# RFID_DC_Motor_Stm32.net
KiCad netlist of a schematic drawn in Altium Designer
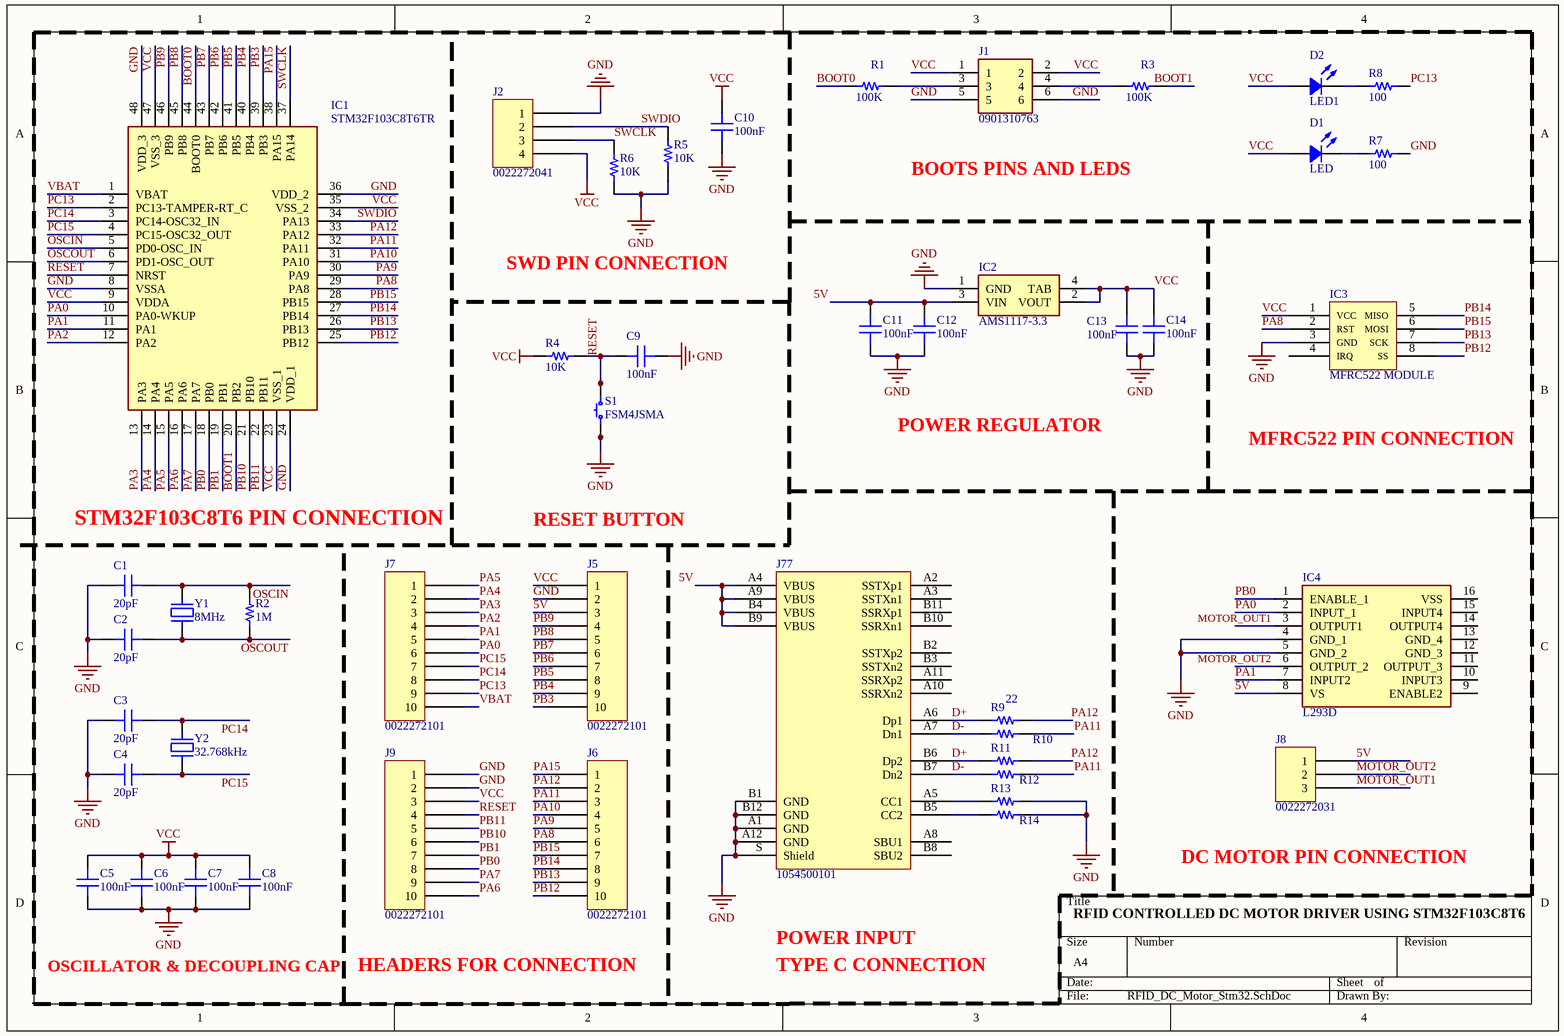
[diagram p0: RFID_DC_Motor_Stm32.SchDoc]

(export (version "E")
  (design (tool "Eeschema 10.0.6"))
  (components
    (comp (ref "C1")
      (value "20pF")
      (footprint "CAP 0805_2012")
      (description "CAP CER 0.1UF 16V Y5V 0805")
      (fields (field (name "PART NUMBER") "C0805C104M4VACTU") (field (name "MANUFACTURER") "KEMET"))
      (libsource (lib "Celestial Altium Library - altium_library") (part "Capacitor"))
    )
    (comp (ref "C2")
      (value "20pF")
      (footprint "CAP 0805_2012")
      (description "CAP CER 0.1UF 16V Y5V 0805")
      (fields (field (name "PART NUMBER") "C0805C104M4VACTU") (field (name "MANUFACTURER") "KEMET"))
      (libsource (lib "Celestial Altium Library - altium_library") (part "Capacitor"))
    )
    (comp (ref "C3")
      (value "20pF")
      (footprint "CAP 0805_2012")
      (description "CAP CER 0.1UF 16V Y5V 0805")
      (fields (field (name "PART NUMBER") "C0805C104M4VACTU") (field (name "MANUFACTURER") "KEMET"))
      (libsource (lib "Celestial Altium Library - altium_library") (part "Capacitor"))
    )
    (comp (ref "C4")
      (value "20pF")
      (footprint "CAP 0805_2012")
      (description "CAP CER 0.1UF 16V Y5V 0805")
      (fields (field (name "PART NUMBER") "C0805C104M4VACTU") (field (name "MANUFACTURER") "KEMET"))
      (libsource (lib "Celestial Altium Library - altium_library") (part "Capacitor"))
    )
    (comp (ref "C5")
      (value "100nF")
      (footprint "CAP 0805_2012")
      (description "CAP CER 0.1UF 16V Y5V 0805")
      (fields (field (name "PART NUMBER") "C0805C104M4VACTU") (field (name "MANUFACTURER") "KEMET"))
      (libsource (lib "Celestial Altium Library - altium_library") (part "Capacitor"))
    )
    (comp (ref "C6")
      (value "100nF")
      (footprint "CAP 0805_2012")
      (description "CAP CER 0.1UF 16V Y5V 0805")
      (fields (field (name "PART NUMBER") "C0805C104M4VACTU") (field (name "MANUFACTURER") "KEMET"))
      (libsource (lib "Celestial Altium Library - altium_library") (part "Capacitor"))
    )
    (comp (ref "C7")
      (value "100nF")
      (footprint "CAP 0805_2012")
      (description "CAP CER 0.1UF 16V Y5V 0805")
      (fields (field (name "PART NUMBER") "C0805C104M4VACTU") (field (name "MANUFACTURER") "KEMET"))
      (libsource (lib "Celestial Altium Library - altium_library") (part "Capacitor"))
    )
    (comp (ref "C8")
      (value "100nF")
      (footprint "CAP 0805_2012")
      (description "CAP CER 0.1UF 16V Y5V 0805")
      (fields (field (name "PART NUMBER") "C0805C104M4VACTU") (field (name "MANUFACTURER") "KEMET"))
      (libsource (lib "Celestial Altium Library - altium_library") (part "Capacitor"))
    )
    (comp (ref "C9")
      (value "100nF")
      (footprint "CAP 0805_2012")
      (description "CAP CER 0.1UF 16V Y5V 0805")
      (fields (field (name "PART NUMBER") "C0805C104M4VACTU") (field (name "MANUFACTURER") "KEMET"))
      (libsource (lib "Celestial Altium Library - altium_library") (part "Capacitor"))
    )
    (comp (ref "C10")
      (value "100nF")
      (footprint "CAP 0805_2012")
      (description "CAP CER 0.1UF 16V Y5V 0805")
      (fields (field (name "PART NUMBER") "C0805C104M4VACTU") (field (name "MANUFACTURER") "KEMET"))
      (libsource (lib "Celestial Altium Library - altium_library") (part "Capacitor"))
    )
    (comp (ref "C11")
      (value "100nF")
      (footprint "CAP 0805_2012")
      (description "CAP CER 0.1UF 16V Y5V 0805")
      (fields (field (name "PART NUMBER") "C0805C104M4VACTU") (field (name "MANUFACTURER") "KEMET"))
      (libsource (lib "Celestial Altium Library - altium_library") (part "Capacitor"))
    )
    (comp (ref "C12")
      (value "100nF")
      (footprint "CAP 0805_2012")
      (description "CAP CER 0.1UF 16V Y5V 0805")
      (fields (field (name "PART NUMBER") "C0805C104M4VACTU") (field (name "MANUFACTURER") "KEMET"))
      (libsource (lib "Celestial Altium Library - altium_library") (part "Capacitor"))
    )
    (comp (ref "C13")
      (value "100nF")
      (footprint "CAP 0805_2012")
      (description "CAP CER 0.1UF 16V Y5V 0805")
      (fields (field (name "PART NUMBER") "C0805C104M4VACTU") (field (name "MANUFACTURER") "KEMET"))
      (libsource (lib "Celestial Altium Library - altium_library") (part "Capacitor"))
    )
    (comp (ref "C14")
      (value "100nF")
      (footprint "CAP 0805_2012")
      (description "CAP CER 0.1UF 16V Y5V 0805")
      (fields (field (name "PART NUMBER") "C0805C104M4VACTU") (field (name "MANUFACTURER") "KEMET"))
      (libsource (lib "Celestial Altium Library - altium_library") (part "Capacitor"))
    )
    (comp (ref "D1")
      (value "LED")
      (footprint "CREE J 2835")
      (description "LED WHITE  4000K JE2835 3V")
      (fields
        (field (name "PART NUMBER") "JE2835AWT-R-U40GA0000-N0000001")
        (field (name "MANUFACTURER") "Cree Inc.")
      )
      (libsource (lib "Celestial Altium Library - altium_library") (part "LED"))
    )
    (comp (ref "D2")
      (value "LED1")
      (footprint "CREE J 2835")
      (description "LED WHITE  4000K JE2835 3V")
      (fields
        (field (name "PART NUMBER") "JE2835AWT-R-U40GA0000-N0000001")
        (field (name "MANUFACTURER") "Cree Inc.")
      )
      (libsource (lib "Celestial Altium Library - altium_library") (part "LED"))
    )
    (comp (ref "IC1")
      (value "STM32F103C8T6TR")
      (footprint "SamacSys:QFP50P900X900X160-48N")
      (description "Integrated Circuit")
      (fields (field (name "MOUSER PART NUMBER") "511-STM32F103C8T6TR"))
      (libsource (lib "SamacSys") (part "STM32F103C8T6TR"))
    )
    (comp (ref "IC2")
      (value "AMS1117-3.3")
      (footprint "SamacSys:SOT229P700X180-4N")
      (description "Integrated Circuit")
      (libsource (lib "SamacSys") (part "AMS1117-3.3"))
    )
    (comp (ref "IC3")
      (value "MFRC522 MODULE")
      (footprint "RC522")
      (description "RFID MODULE")
      (libsource (lib "SamacSys") (part "MFRC522 MODULE"))
    )
    (comp (ref "IC4")
      (value "L293D")
      (footprint "DIP880W50P254L2000H510Q16N")
      (description "Integrated Circuit")
      (fields (field (name "MOUSER PART NUMBER") "511-L293D"))
      (libsource (lib "SamacSys") (part "L293D"))
    )
    (comp (ref "J1")
      (value "0901310763")
      (footprint "SamacSys:HDRV6W90P254_2X3_762X500X560P")
      (description "Connector")
      (libsource (lib "SamacSys") (part "0901310763"))
    )
    (comp (ref "J2")
      (value "0022272041")
      (footprint "MOLEX KK 0022272041")
      (description "CONN HEADER VERT 4POS 2.54MM")
      (fields (field (name "MANUFACTURER") "Molex"))
      (libsource (lib "Celestial Altium Library - altium_library") (part "4 Pin"))
    )
    (comp (ref "J5")
      (value "0022272101")
      (footprint "MOLEX KK 0022272101")
      (description "CONN HEADER VERT 10POS 2.54MM")
      (fields (field (name "MANUFACTURER") "Molex"))
      (libsource (lib "Celestial Altium Library - altium_library") (part "10 Pin"))
    )
    (comp (ref "J6")
      (value "0022272101")
      (footprint "MOLEX KK 0022272101")
      (description "CONN HEADER VERT 10POS 2.54MM")
      (fields (field (name "MANUFACTURER") "Molex"))
      (libsource (lib "Celestial Altium Library - altium_library") (part "10 Pin"))
    )
    (comp (ref "J7")
      (value "0022272101")
      (footprint "MOLEX KK 0022272101")
      (description "CONN HEADER VERT 10POS 2.54MM")
      (fields (field (name "MANUFACTURER") "Molex"))
      (libsource (lib "") (part "10 Pin_1"))
    )
    (comp (ref "J8")
      (value "0022272031")
      (footprint "MOLEX KK 0022272031")
      (description "CONN HEADER VERT 3POS 2.54MM")
      (fields (field (name "MANUFACTURER") "Molex"))
      (libsource (lib "Celestial Altium Library - altium_library") (part "3 Pin"))
    )
    (comp (ref "J9")
      (value "0022272101")
      (footprint "MOLEX KK 0022272101")
      (description "CONN HEADER VERT 10POS 2.54MM")
      (fields (field (name "MANUFACTURER") "Molex"))
      (libsource (lib "") (part "10 Pin_1"))
    )
    (comp (ref "J77")
      (value "1054500101")
      (footprint "Molex 1054500101")
      (description "CONN RCP USB3.1 TYPEC 24P SMD RA")
      (fields (field (name "MANUFACTURER") "Molex"))
      (libsource (lib "Celestial Altium Library - altium_library") (part "USB 3.0 Type C"))
    )
    (comp (ref "R1")
      (value "100K")
      (footprint "RES 0805_2012")
      (description "RES 931K OHM 1% 1/8W 0805")
      (fields
        (field (name "PART NUMBER") "RMCF0805FT931K")
        (field (name "MANUFACTURER") "Stackpole Electronics Inc")
      )
      (libsource (lib "Celestial Altium Library - altium_library") (part "Resistor"))
    )
    (comp (ref "R2")
      (value "1M")
      (footprint "RES 0805_2012")
      (description "RES 931K OHM 1% 1/8W 0805")
      (fields
        (field (name "PART NUMBER") "RMCF0805FT931K")
        (field (name "MANUFACTURER") "Stackpole Electronics Inc")
      )
      (libsource (lib "Celestial Altium Library - altium_library") (part "Resistor"))
    )
    (comp (ref "R3")
      (value "100K")
      (footprint "RES 0805_2012")
      (description "RES 931K OHM 1% 1/8W 0805")
      (fields
        (field (name "PART NUMBER") "RMCF0805FT931K")
        (field (name "MANUFACTURER") "Stackpole Electronics Inc")
      )
      (libsource (lib "Celestial Altium Library - altium_library") (part "Resistor"))
    )
    (comp (ref "R4")
      (value "10K")
      (footprint "RES 0805_2012")
      (description "RES 931K OHM 1% 1/8W 0805")
      (fields
        (field (name "PART NUMBER") "RMCF0805FT931K")
        (field (name "MANUFACTURER") "Stackpole Electronics Inc")
      )
      (libsource (lib "Celestial Altium Library - altium_library") (part "Resistor"))
    )
    (comp (ref "R5")
      (value "10K")
      (footprint "RES 0805_2012")
      (description "RES 931K OHM 1% 1/8W 0805")
      (fields
        (field (name "PART NUMBER") "RMCF0805FT931K")
        (field (name "MANUFACTURER") "Stackpole Electronics Inc")
      )
      (libsource (lib "Celestial Altium Library - altium_library") (part "Resistor"))
    )
    (comp (ref "R6")
      (value "10K")
      (footprint "RES 0805_2012")
      (description "RES 931K OHM 1% 1/8W 0805")
      (fields
        (field (name "PART NUMBER") "RMCF0805FT931K")
        (field (name "MANUFACTURER") "Stackpole Electronics Inc")
      )
      (libsource (lib "Celestial Altium Library - altium_library") (part "Resistor"))
    )
    (comp (ref "R7")
      (value "100")
      (footprint "RES 0805_2012")
      (description "RES 931K OHM 1% 1/8W 0805")
      (fields
        (field (name "PART NUMBER") "RMCF0805FT931K")
        (field (name "MANUFACTURER") "Stackpole Electronics Inc")
      )
      (libsource (lib "Celestial Altium Library - altium_library") (part "Resistor"))
    )
    (comp (ref "R8")
      (value "100")
      (footprint "RES 0805_2012")
      (description "RES 931K OHM 1% 1/8W 0805")
      (fields
        (field (name "PART NUMBER") "RMCF0805FT931K")
        (field (name "MANUFACTURER") "Stackpole Electronics Inc")
      )
      (libsource (lib "Celestial Altium Library - altium_library") (part "Resistor"))
    )
    (comp (ref "R9")
      (value "22")
      (footprint "RES 0805_2012")
      (description "RES 931K OHM 1% 1/8W 0805")
      (fields
        (field (name "PART NUMBER") "RMCF0805FT931K")
        (field (name "MANUFACTURER") "Stackpole Electronics Inc")
      )
      (libsource (lib "Celestial Altium Library - altium_library") (part "Resistor"))
    )
    (comp (ref "R10")
      (value "~")
      (footprint "RES 0805_2012")
      (description "RES 931K OHM 1% 1/8W 0805")
      (fields
        (field (name "PART NUMBER") "RMCF0805FT931K")
        (field (name "MANUFACTURER") "Stackpole Electronics Inc")
      )
      (libsource (lib "Celestial Altium Library - altium_library") (part "Resistor"))
    )
    (comp (ref "R11")
      (value "~")
      (footprint "RES 0805_2012")
      (description "RES 931K OHM 1% 1/8W 0805")
      (fields
        (field (name "PART NUMBER") "RMCF0805FT931K")
        (field (name "MANUFACTURER") "Stackpole Electronics Inc")
      )
      (libsource (lib "Celestial Altium Library - altium_library") (part "Resistor"))
    )
    (comp (ref "R12")
      (value "~")
      (footprint "RES 0805_2012")
      (description "RES 931K OHM 1% 1/8W 0805")
      (fields
        (field (name "PART NUMBER") "RMCF0805FT931K")
        (field (name "MANUFACTURER") "Stackpole Electronics Inc")
      )
      (libsource (lib "Celestial Altium Library - altium_library") (part "Resistor"))
    )
    (comp (ref "R13")
      (value "~")
      (footprint "RES 0805_2012")
      (description "RES 931K OHM 1% 1/8W 0805")
      (fields
        (field (name "PART NUMBER") "RMCF0805FT931K")
        (field (name "MANUFACTURER") "Stackpole Electronics Inc")
      )
      (libsource (lib "Celestial Altium Library - altium_library") (part "Resistor"))
    )
    (comp (ref "R14")
      (value "~")
      (footprint "RES 0805_2012")
      (description "RES 931K OHM 1% 1/8W 0805")
      (fields
        (field (name "PART NUMBER") "RMCF0805FT931K")
        (field (name "MANUFACTURER") "Stackpole Electronics Inc")
      )
      (libsource (lib "Celestial Altium Library - altium_library") (part "Resistor"))
    )
    (comp (ref "S1")
      (value "FSM4JSMA")
      (footprint "TE FSM4JSMA")
      (description "SWITCH TACTILE SPST-NO 0.05A 24V")
      (fields (field (name "MANUFACTURER") "TE Connectivity ALCOSWITCH Switches"))
      (libsource (lib "Celestial Altium Library - altium_library") (part "SPST-NO 4 PIN"))
    )
    (comp (ref "Y1")
      (value "8MHz")
      (footprint "ABRACON ABLS")
      (description "CRYSTAL 8.0000MHZ 18PF SMD")
      (fields (field (name "PART NUMBER") "ABLS-8.000MHZ-D-T") (field (name "MANUFACTURER") "Abracon LLC"))
      (libsource (lib "Celestial Altium Library - altium_library") (part "Abracon Crystal ABLS"))
    )
    (comp (ref "Y2")
      (value "32.768kHz")
      (footprint "ABRACON ABS07")
      (description "CRYSTAL 32.768KHZ 9PF SMD")
      (fields
        (field (name "PART NUMBER") "ABS07-32.768KHZ-9-1-T")
        (field (name "MANUFACTURER") "Abracon LLC")
      )
      (libsource (lib "Celestial Altium Library - altium_library") (part "Abracon Crystal ABS07"))
    )
  )
  (nets
    (net (code "1") (name "/5V") (class "Default")
      (node (ref "C11") (pin "2") (pinfunction "2_2") (pintype "passive"))
      (node (ref "C12") (pin "2") (pinfunction "2_2") (pintype "passive"))
      (node (ref "IC2") (pin "3") (pinfunction "VIN_3") (pintype "passive"))
      (node (ref "IC4") (pin "8") (pinfunction "VS_8") (pintype "passive"))
      (node (ref "J5") (pin "3") (pinfunction "3_3") (pintype "passive"))
      (node (ref "J77") (pin "A4") (pinfunction "VBUS_A4") (pintype "passive"))
      (node (ref "J77") (pin "A9") (pinfunction "VBUS_A9") (pintype "passive"))
      (node (ref "J77") (pin "B4") (pinfunction "VBUS_B4") (pintype "passive"))
      (node (ref "J77") (pin "B9") (pinfunction "VBUS_B9") (pintype "passive"))
      (node (ref "J8") (pin "1") (pinfunction "1_1") (pintype "passive"))
    )
    (net (code "2") (name "/BOOT0") (class "Default")
      (node (ref "IC1") (pin "44") (pinfunction "BOOT0_44") (pintype "passive"))
      (node (ref "R1") (pin "1") (pinfunction "1_1") (pintype "passive"))
    )
    (net (code "3") (name "/BOOT1") (class "Default")
      (node (ref "IC1") (pin "20") (pinfunction "PB2_20") (pintype "passive"))
      (node (ref "R3") (pin "2") (pinfunction "2_2") (pintype "passive"))
    )
    (net (code "4") (name "/D+") (class "Default")
      (node (ref "J77") (pin "A6") (pinfunction "Dp1_A6") (pintype "passive"))
      (node (ref "J77") (pin "B6") (pinfunction "Dp2_B6") (pintype "passive"))
      (node (ref "R11") (pin "2") (pinfunction "2_2") (pintype "passive"))
      (node (ref "R9") (pin "2") (pinfunction "2_2") (pintype "passive"))
    )
    (net (code "5") (name "/D-") (class "Default")
      (node (ref "J77") (pin "A7") (pinfunction "Dn1_A7") (pintype "passive"))
      (node (ref "J77") (pin "B7") (pinfunction "Dn2_B7") (pintype "passive"))
      (node (ref "R10") (pin "2") (pinfunction "2_2") (pintype "passive"))
      (node (ref "R12") (pin "2") (pinfunction "2_2") (pintype "passive"))
    )
    (net (code "6") (name "/MOTOR_OUT1") (class "Default")
      (node (ref "IC4") (pin "3") (pinfunction "OUTPUT1_3") (pintype "passive"))
      (node (ref "J8") (pin "3") (pinfunction "3_3") (pintype "passive"))
    )
    (net (code "7") (name "/MOTOR_OUT2") (class "Default")
      (node (ref "IC4") (pin "6") (pinfunction "OUTPUT_2_6") (pintype "passive"))
      (node (ref "J8") (pin "2") (pinfunction "2_2") (pintype "passive"))
    )
    (net (code "8") (name "/OSCIN") (class "Default")
      (node (ref "C1") (pin "2") (pinfunction "2_2") (pintype "passive"))
      (node (ref "IC1") (pin "5") (pinfunction "PD0-OSC_IN_5") (pintype "passive"))
      (node (ref "R2") (pin "2") (pinfunction "2_2") (pintype "passive"))
      (node (ref "Y1") (pin "2") (pinfunction "2_2") (pintype "passive"))
    )
    (net (code "9") (name "/OSCOUT") (class "Default")
      (node (ref "C2") (pin "2") (pinfunction "2_2") (pintype "passive"))
      (node (ref "IC1") (pin "6") (pinfunction "PD1-OSC_OUT_6") (pintype "passive"))
      (node (ref "R2") (pin "1") (pinfunction "1_1") (pintype "passive"))
      (node (ref "Y1") (pin "1") (pinfunction "1_1") (pintype "passive"))
    )
    (net (code "10") (name "/PA0") (class "Default")
      (node (ref "IC1") (pin "10") (pinfunction "PA0-WKUP_10") (pintype "passive"))
      (node (ref "IC4") (pin "2") (pinfunction "INPUT_1_2") (pintype "passive"))
      (node (ref "J7") (pin "6") (pinfunction "6_6") (pintype "passive"))
    )
    (net (code "11") (name "/PA1") (class "Default")
      (node (ref "IC1") (pin "11") (pinfunction "PA1_11") (pintype "passive"))
      (node (ref "IC4") (pin "7") (pinfunction "INPUT2_7") (pintype "passive"))
      (node (ref "J7") (pin "5") (pinfunction "5_5") (pintype "passive"))
    )
    (net (code "12") (name "/PA2") (class "Default")
      (node (ref "IC1") (pin "12") (pinfunction "PA2_12") (pintype "passive"))
      (node (ref "J7") (pin "4") (pinfunction "4_4") (pintype "passive"))
    )
    (net (code "13") (name "/PA3") (class "Default")
      (node (ref "IC1") (pin "13") (pinfunction "PA3_13") (pintype "passive"))
      (node (ref "J7") (pin "3") (pinfunction "3_3") (pintype "passive"))
    )
    (net (code "14") (name "/PA4") (class "Default")
      (node (ref "IC1") (pin "14") (pinfunction "PA4_14") (pintype "passive"))
      (node (ref "J7") (pin "2") (pinfunction "2_2") (pintype "passive"))
    )
    (net (code "15") (name "/PA5") (class "Default")
      (node (ref "IC1") (pin "15") (pinfunction "PA5_15") (pintype "passive"))
      (node (ref "J7") (pin "1") (pinfunction "1_1") (pintype "passive"))
    )
    (net (code "16") (name "/PA6") (class "Default")
      (node (ref "IC1") (pin "16") (pinfunction "PA6_16") (pintype "passive"))
      (node (ref "J9") (pin "10") (pinfunction "10_10") (pintype "passive"))
    )
    (net (code "17") (name "/PA7") (class "Default")
      (node (ref "IC1") (pin "17") (pinfunction "PA7_17") (pintype "passive"))
      (node (ref "J9") (pin "9") (pinfunction "9_9") (pintype "passive"))
    )
    (net (code "18") (name "/PA8") (class "Default")
      (node (ref "IC1") (pin "29") (pinfunction "PA8_29") (pintype "passive"))
      (node (ref "IC3") (pin "2") (pinfunction "RST_2") (pintype "passive"))
      (node (ref "J6") (pin "6") (pinfunction "6_6") (pintype "passive"))
    )
    (net (code "19") (name "/PA9") (class "Default")
      (node (ref "IC1") (pin "30") (pinfunction "PA9_30") (pintype "passive"))
      (node (ref "J6") (pin "5") (pinfunction "5_5") (pintype "passive"))
    )
    (net (code "20") (name "/PA10") (class "Default")
      (node (ref "IC1") (pin "31") (pinfunction "PA10_31") (pintype "passive"))
      (node (ref "J6") (pin "4") (pinfunction "4_4") (pintype "passive"))
    )
    (net (code "21") (name "/PA11") (class "Default")
      (node (ref "IC1") (pin "32") (pinfunction "PA11_32") (pintype "passive"))
      (node (ref "J6") (pin "3") (pinfunction "3_3") (pintype "passive"))
      (node (ref "R10") (pin "1") (pinfunction "1_1") (pintype "passive"))
      (node (ref "R12") (pin "1") (pinfunction "1_1") (pintype "passive"))
    )
    (net (code "22") (name "/PA12") (class "Default")
      (node (ref "IC1") (pin "33") (pinfunction "PA12_33") (pintype "passive"))
      (node (ref "J6") (pin "2") (pinfunction "2_2") (pintype "passive"))
      (node (ref "R11") (pin "1") (pinfunction "1_1") (pintype "passive"))
      (node (ref "R9") (pin "1") (pinfunction "1_1") (pintype "passive"))
    )
    (net (code "23") (name "/PA15") (class "Default")
      (node (ref "IC1") (pin "38") (pinfunction "PA15_38") (pintype "passive"))
      (node (ref "J6") (pin "1") (pinfunction "1_1") (pintype "passive"))
    )
    (net (code "24") (name "/PB0") (class "Default")
      (node (ref "IC1") (pin "18") (pinfunction "PB0_18") (pintype "passive"))
      (node (ref "IC4") (pin "1") (pinfunction "ENABLE_1_1") (pintype "passive"))
      (node (ref "J9") (pin "8") (pinfunction "8_8") (pintype "passive"))
    )
    (net (code "25") (name "/PB1") (class "Default")
      (node (ref "IC1") (pin "19") (pinfunction "PB1_19") (pintype "passive"))
      (node (ref "J9") (pin "7") (pinfunction "7_7") (pintype "passive"))
    )
    (net (code "26") (name "/PB3") (class "Default")
      (node (ref "IC1") (pin "39") (pinfunction "PB3_39") (pintype "passive"))
      (node (ref "J5") (pin "10") (pinfunction "10_10") (pintype "passive"))
    )
    (net (code "27") (name "/PB4") (class "Default")
      (node (ref "IC1") (pin "40") (pinfunction "PB4_40") (pintype "passive"))
      (node (ref "J5") (pin "9") (pinfunction "9_9") (pintype "passive"))
    )
    (net (code "28") (name "/PB5") (class "Default")
      (node (ref "IC1") (pin "41") (pinfunction "PB5_41") (pintype "passive"))
      (node (ref "J5") (pin "8") (pinfunction "8_8") (pintype "passive"))
    )
    (net (code "29") (name "/PB6") (class "Default")
      (node (ref "IC1") (pin "42") (pinfunction "PB6_42") (pintype "passive"))
      (node (ref "J5") (pin "7") (pinfunction "7_7") (pintype "passive"))
    )
    (net (code "30") (name "/PB7") (class "Default")
      (node (ref "IC1") (pin "43") (pinfunction "PB7_43") (pintype "passive"))
      (node (ref "J5") (pin "6") (pinfunction "6_6") (pintype "passive"))
    )
    (net (code "31") (name "/PB8") (class "Default")
      (node (ref "IC1") (pin "45") (pinfunction "PB8_45") (pintype "passive"))
      (node (ref "J5") (pin "5") (pinfunction "5_5") (pintype "passive"))
    )
    (net (code "32") (name "/PB9") (class "Default")
      (node (ref "IC1") (pin "46") (pinfunction "PB9_46") (pintype "passive"))
      (node (ref "J5") (pin "4") (pinfunction "4_4") (pintype "passive"))
    )
    (net (code "33") (name "/PB10") (class "Default")
      (node (ref "IC1") (pin "21") (pinfunction "PB10_21") (pintype "passive"))
      (node (ref "J9") (pin "6") (pinfunction "6_6") (pintype "passive"))
    )
    (net (code "34") (name "/PB11") (class "Default")
      (node (ref "IC1") (pin "22") (pinfunction "PB11_22") (pintype "passive"))
      (node (ref "J9") (pin "5") (pinfunction "5_5") (pintype "passive"))
    )
    (net (code "35") (name "/PB12") (class "Default")
      (node (ref "IC1") (pin "25") (pinfunction "PB12_25") (pintype "passive"))
      (node (ref "IC3") (pin "8") (pinfunction "SS_8") (pintype "passive"))
      (node (ref "J6") (pin "10") (pinfunction "10_10") (pintype "passive"))
    )
    (net (code "36") (name "/PB13") (class "Default")
      (node (ref "IC1") (pin "26") (pinfunction "PB13_26") (pintype "passive"))
      (node (ref "IC3") (pin "7") (pinfunction "SCK_7") (pintype "passive"))
      (node (ref "J6") (pin "9") (pinfunction "9_9") (pintype "passive"))
    )
    (net (code "37") (name "/PB14") (class "Default")
      (node (ref "IC1") (pin "27") (pinfunction "PB14_27") (pintype "passive"))
      (node (ref "IC3") (pin "5") (pinfunction "MISO_5") (pintype "passive"))
      (node (ref "J6") (pin "8") (pinfunction "8_8") (pintype "passive"))
    )
    (net (code "38") (name "/PB15") (class "Default")
      (node (ref "IC1") (pin "28") (pinfunction "PB15_28") (pintype "passive"))
      (node (ref "IC3") (pin "6") (pinfunction "MOSI_6") (pintype "passive"))
      (node (ref "J6") (pin "7") (pinfunction "7_7") (pintype "passive"))
    )
    (net (code "39") (name "/PC13") (class "Default")
      (node (ref "IC1") (pin "2") (pinfunction "PC13-TAMPER-RT_C_2") (pintype "passive"))
      (node (ref "J7") (pin "9") (pinfunction "9_9") (pintype "passive"))
      (node (ref "R8") (pin "2") (pinfunction "2_2") (pintype "passive"))
    )
    (net (code "40") (name "/PC14") (class "Default")
      (node (ref "C3") (pin "2") (pinfunction "2_2") (pintype "passive"))
      (node (ref "IC1") (pin "3") (pinfunction "PC14-OSC32_IN_3") (pintype "passive"))
      (node (ref "J7") (pin "8") (pinfunction "8_8") (pintype "passive"))
      (node (ref "Y2") (pin "1") (pinfunction "1_1") (pintype "passive"))
    )
    (net (code "41") (name "/PC15") (class "Default")
      (node (ref "C4") (pin "2") (pinfunction "2_2") (pintype "passive"))
      (node (ref "IC1") (pin "4") (pinfunction "PC15-OSC32_OUT_4") (pintype "passive"))
      (node (ref "J7") (pin "7") (pinfunction "7_7") (pintype "passive"))
      (node (ref "Y2") (pin "2") (pinfunction "2_2") (pintype "passive"))
    )
    (net (code "42") (name "/RESET") (class "Default")
      (node (ref "C9") (pin "2") (pinfunction "2_2") (pintype "passive"))
      (node (ref "IC1") (pin "7") (pinfunction "NRST_7") (pintype "passive"))
      (node (ref "J9") (pin "4") (pinfunction "4_4") (pintype "passive"))
      (node (ref "R4") (pin "1") (pinfunction "1_1") (pintype "passive"))
      (node (ref "S1") (pin "3") (pinfunction "3_3") (pintype "passive"))
      (node (ref "S1") (pin "4") (pinfunction "4_4") (pintype "passive"))
    )
    (net (code "43") (name "/SWCLK") (class "Default")
      (node (ref "IC1") (pin "37") (pinfunction "PA14_37") (pintype "passive"))
      (node (ref "J2") (pin "3") (pinfunction "3_3") (pintype "passive"))
      (node (ref "R6") (pin "1") (pinfunction "1_1") (pintype "passive"))
    )
    (net (code "44") (name "/SWDIO") (class "Default")
      (node (ref "IC1") (pin "34") (pinfunction "PA13_34") (pintype "passive"))
      (node (ref "J2") (pin "2") (pinfunction "2_2") (pintype "passive"))
      (node (ref "R5") (pin "2") (pinfunction "2_2") (pintype "passive"))
    )
    (net (code "45") (name "/VBAT") (class "Default")
      (node (ref "IC1") (pin "1") (pinfunction "VBAT_1") (pintype "passive"))
      (node (ref "J7") (pin "10") (pinfunction "10_10") (pintype "passive"))
    )
    (net (code "46") (name "GND") (class "Default")
      (node (ref "C1") (pin "1") (pinfunction "1_1") (pintype "passive"))
      (node (ref "C10") (pin "1") (pinfunction "1_1") (pintype "passive"))
      (node (ref "C11") (pin "1") (pinfunction "1_1") (pintype "passive"))
      (node (ref "C12") (pin "1") (pinfunction "1_1") (pintype "passive"))
      (node (ref "C13") (pin "1") (pinfunction "1_1") (pintype "passive"))
      (node (ref "C14") (pin "1") (pinfunction "1_1") (pintype "passive"))
      (node (ref "C2") (pin "1") (pinfunction "1_1") (pintype "passive"))
      (node (ref "C3") (pin "1") (pinfunction "1_1") (pintype "passive"))
      (node (ref "C4") (pin "1") (pinfunction "1_1") (pintype "passive"))
      (node (ref "C5") (pin "1") (pinfunction "1_1") (pintype "passive"))
      (node (ref "C6") (pin "1") (pinfunction "1_1") (pintype "passive"))
      (node (ref "C7") (pin "1") (pinfunction "1_1") (pintype "passive"))
      (node (ref "C8") (pin "1") (pinfunction "1_1") (pintype "passive"))
      (node (ref "C9") (pin "1") (pinfunction "1_1") (pintype "passive"))
      (node (ref "IC1") (pin "24") (pinfunction "VDD_1_24") (pintype "passive"))
      (node (ref "IC1") (pin "36") (pinfunction "VDD_2_36") (pintype "passive"))
      (node (ref "IC1") (pin "48") (pinfunction "VDD_3_48") (pintype "passive"))
      (node (ref "IC1") (pin "8") (pinfunction "VSSA_8") (pintype "passive"))
      (node (ref "IC2") (pin "1") (pinfunction "GND_1") (pintype "passive"))
      (node (ref "IC3") (pin "3") (pinfunction "GND_3") (pintype "passive"))
      (node (ref "IC4") (pin "4") (pinfunction "GND_1_4") (pintype "passive"))
      (node (ref "IC4") (pin "5") (pinfunction "GND_2_5") (pintype "passive"))
      (node (ref "J1") (pin "5") (pinfunction "5_5") (pintype "passive"))
      (node (ref "J1") (pin "6") (pinfunction "6_6") (pintype "passive"))
      (node (ref "J2") (pin "1") (pinfunction "1_1") (pintype "passive"))
      (node (ref "J5") (pin "2") (pinfunction "2_2") (pintype "passive"))
      (node (ref "J77") (pin "A1") (pinfunction "GND_A1") (pintype "passive"))
      (node (ref "J77") (pin "A12") (pinfunction "GND_A12") (pintype "passive"))
      (node (ref "J77") (pin "B1") (pinfunction "GND_B1") (pintype "passive"))
      (node (ref "J77") (pin "B12") (pinfunction "GND_B12") (pintype "passive"))
      (node (ref "J77") (pin "S") (pinfunction "Shield_S") (pintype "passive"))
      (node (ref "J9") (pin "1") (pinfunction "1_1") (pintype "passive"))
      (node (ref "J9") (pin "2") (pinfunction "2_2") (pintype "passive"))
      (node (ref "R13") (pin "1") (pinfunction "1_1") (pintype "passive"))
      (node (ref "R14") (pin "1") (pinfunction "1_1") (pintype "passive"))
      (node (ref "R5") (pin "1") (pinfunction "1_1") (pintype "passive"))
      (node (ref "R6") (pin "2") (pinfunction "2_2") (pintype "passive"))
      (node (ref "R7") (pin "2") (pinfunction "2_2") (pintype "passive"))
      (node (ref "S1") (pin "1") (pinfunction "1_1") (pintype "passive"))
      (node (ref "S1") (pin "2") (pinfunction "2_2") (pintype "passive"))
    )
    (net (code "47") (name "Net-(D1-Pad2)") (class "Default")
      (node (ref "D1") (pin "2") (pinfunction "2_2") (pintype "passive"))
      (node (ref "R7") (pin "1") (pinfunction "1_1") (pintype "passive"))
    )
    (net (code "48") (name "Net-(D2-Pad2)") (class "Default")
      (node (ref "D2") (pin "2") (pinfunction "2_2") (pintype "passive"))
      (node (ref "R8") (pin "1") (pinfunction "1_1") (pintype "passive"))
    )
    (net (code "49") (name "Net-(J1-Pad3)") (class "Default")
      (node (ref "J1") (pin "3") (pinfunction "3_3") (pintype "passive"))
      (node (ref "R1") (pin "2") (pinfunction "2_2") (pintype "passive"))
    )
    (net (code "50") (name "Net-(J1-Pad4)") (class "Default")
      (node (ref "J1") (pin "4") (pinfunction "4_4") (pintype "passive"))
      (node (ref "R3") (pin "1") (pinfunction "1_1") (pintype "passive"))
    )
    (net (code "51") (name "Net-(J77-CC1)") (class "Default")
      (node (ref "J77") (pin "A5") (pinfunction "CC1_A5") (pintype "passive"))
      (node (ref "R13") (pin "2") (pinfunction "2_2") (pintype "passive"))
    )
    (net (code "52") (name "Net-(J77-CC2)") (class "Default")
      (node (ref "J77") (pin "B5") (pinfunction "CC2_B5") (pintype "passive"))
      (node (ref "R14") (pin "2") (pinfunction "2_2") (pintype "passive"))
    )
    (net (code "53") (name "VCC") (class "Default")
      (node (ref "C10") (pin "2") (pinfunction "2_2") (pintype "passive"))
      (node (ref "C13") (pin "2") (pinfunction "2_2") (pintype "passive"))
      (node (ref "C14") (pin "2") (pinfunction "2_2") (pintype "passive"))
      (node (ref "C5") (pin "2") (pinfunction "2_2") (pintype "passive"))
      (node (ref "C6") (pin "2") (pinfunction "2_2") (pintype "passive"))
      (node (ref "C7") (pin "2") (pinfunction "2_2") (pintype "passive"))
      (node (ref "C8") (pin "2") (pinfunction "2_2") (pintype "passive"))
      (node (ref "D1") (pin "1") (pinfunction "1_1") (pintype "passive"))
      (node (ref "D2") (pin "1") (pinfunction "1_1") (pintype "passive"))
      (node (ref "IC1") (pin "23") (pinfunction "VSS_1_23") (pintype "passive"))
      (node (ref "IC1") (pin "35") (pinfunction "VSS_2_35") (pintype "passive"))
      (node (ref "IC1") (pin "47") (pinfunction "VSS_3_47") (pintype "passive"))
      (node (ref "IC1") (pin "9") (pinfunction "VDDA_9") (pintype "passive"))
      (node (ref "IC2") (pin "2") (pinfunction "VOUT_2") (pintype "passive"))
      (node (ref "IC2") (pin "4") (pinfunction "TAB_4") (pintype "passive"))
      (node (ref "IC3") (pin "1") (pinfunction "VCC_1") (pintype "passive"))
      (node (ref "J1") (pin "1") (pinfunction "1_1") (pintype "passive"))
      (node (ref "J1") (pin "2") (pinfunction "2_2") (pintype "passive"))
      (node (ref "J2") (pin "4") (pinfunction "4_4") (pintype "passive"))
      (node (ref "J5") (pin "1") (pinfunction "1_1") (pintype "passive"))
      (node (ref "J9") (pin "3") (pinfunction "3_3") (pintype "passive"))
      (node (ref "R4") (pin "2") (pinfunction "2_2") (pintype "passive"))
    )
    (net (code "54") (name "unconnected-(IC3-IRQ-Pad4)") (class "Default")
      (node (ref "IC3") (pin "4") (pinfunction "IRQ_4") (pintype "passive"))
    )
    (net (code "55") (name "unconnected-(IC4-ENABLE2-Pad9)") (class "Default")
      (node (ref "IC4") (pin "9") (pinfunction "ENABLE2_9") (pintype "passive"))
    )
    (net (code "56") (name "unconnected-(IC4-GND_3-Pad12)") (class "Default")
      (node (ref "IC4") (pin "12") (pinfunction "GND_3_12") (pintype "passive"))
    )
    (net (code "57") (name "unconnected-(IC4-GND_4-Pad13)") (class "Default")
      (node (ref "IC4") (pin "13") (pinfunction "GND_4_13") (pintype "passive"))
    )
    (net (code "58") (name "unconnected-(IC4-INPUT3-Pad10)") (class "Default")
      (node (ref "IC4") (pin "10") (pinfunction "INPUT3_10") (pintype "passive"))
    )
    (net (code "59") (name "unconnected-(IC4-INPUT4-Pad15)") (class "Default")
      (node (ref "IC4") (pin "15") (pinfunction "INPUT4_15") (pintype "passive"))
    )
    (net (code "60") (name "unconnected-(IC4-OUTPUT4-Pad14)") (class "Default")
      (node (ref "IC4") (pin "14") (pinfunction "OUTPUT4_14") (pintype "passive"))
    )
    (net (code "61") (name "unconnected-(IC4-OUTPUT_3-Pad11)") (class "Default")
      (node (ref "IC4") (pin "11") (pinfunction "OUTPUT_3_11") (pintype "passive"))
    )
    (net (code "62") (name "unconnected-(IC4-VSS-Pad16)") (class "Default")
      (node (ref "IC4") (pin "16") (pinfunction "VSS_16") (pintype "passive"))
    )
    (net (code "63") (name "unconnected-(J77-SBU1-PadA8)") (class "Default")
      (node (ref "J77") (pin "A8") (pinfunction "SBU1_A8") (pintype "passive"))
    )
    (net (code "64") (name "unconnected-(J77-SBU2-PadB8)") (class "Default")
      (node (ref "J77") (pin "B8") (pinfunction "SBU2_B8") (pintype "passive"))
    )
    (net (code "65") (name "unconnected-(J77-SSRXn1-PadB10)") (class "Default")
      (node (ref "J77") (pin "B10") (pinfunction "SSRXn1_B10") (pintype "passive"))
    )
    (net (code "66") (name "unconnected-(J77-SSRXn2-PadA10)") (class "Default")
      (node (ref "J77") (pin "A10") (pinfunction "SSRXn2_A10") (pintype "passive"))
    )
    (net (code "67") (name "unconnected-(J77-SSRXp1-PadB11)") (class "Default")
      (node (ref "J77") (pin "B11") (pinfunction "SSRXp1_B11") (pintype "passive"))
    )
    (net (code "68") (name "unconnected-(J77-SSRXp2-PadA11)") (class "Default")
      (node (ref "J77") (pin "A11") (pinfunction "SSRXp2_A11") (pintype "passive"))
    )
    (net (code "69") (name "unconnected-(J77-SSTXn1-PadA3)") (class "Default")
      (node (ref "J77") (pin "A3") (pinfunction "SSTXn1_A3") (pintype "passive"))
    )
    (net (code "70") (name "unconnected-(J77-SSTXn2-PadB3)") (class "Default")
      (node (ref "J77") (pin "B3") (pinfunction "SSTXn2_B3") (pintype "passive"))
    )
    (net (code "71") (name "unconnected-(J77-SSTXp1-PadA2)") (class "Default")
      (node (ref "J77") (pin "A2") (pinfunction "SSTXp1_A2") (pintype "passive"))
    )
    (net (code "72") (name "unconnected-(J77-SSTXp2-PadB2)") (class "Default")
      (node (ref "J77") (pin "B2") (pinfunction "SSTXp2_B2") (pintype "passive"))
    )
  )
)
